# pt100.net
KiCad netlist of a schematic drawn in Altium Designer
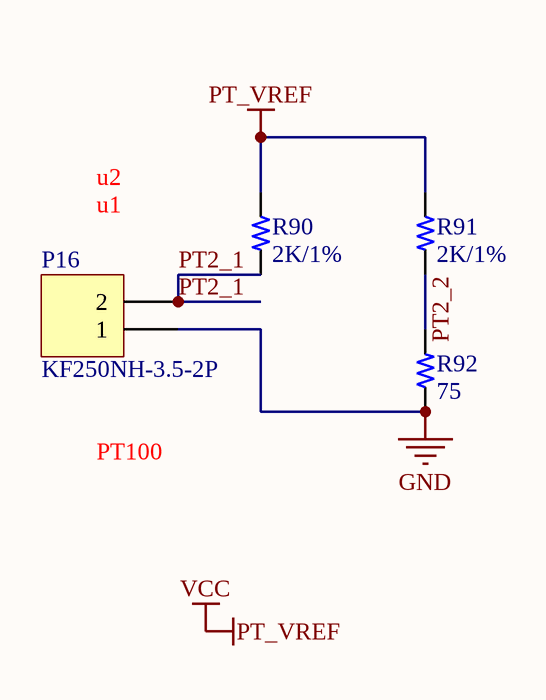
[diagram p0: pt100.SchDoc]

(export (version "E")
  (design (tool "Eeschema 10.0.6"))
  (components
    (comp (ref "P16")
      (value "KF250NH-3.5-2P")
      (footprint "KF250NH-3.5-2P")
      (fields (field (name "PUBLISHER") "Altium Limited"))
      (libsource (lib "Miscellaneous Connectors") (part "Header 2"))
    )
    (comp (ref "R90") (value "2K/1%") (footprint "0603R") (libsource (lib "JRJ_1") (part "R")))
    (comp (ref "R91") (value "2K/1%") (footprint "0603R") (libsource (lib "JRJ_1") (part "R")))
    (comp (ref "R92") (value "75") (footprint "0603R") (libsource (lib "JRJ_1") (part "R")))
  )
  (nets
    (net (code "1") (name "/PT2_1") (class "Default")
      (node (ref "P16") (pin "2") (pinfunction "2_2") (pintype "passive"))
      (node (ref "R90") (pin "1") (pintype "passive"))
    )
    (net (code "2") (name "/PT2_2") (class "Default")
      (node (ref "R91") (pin "1") (pintype "passive"))
      (node (ref "R92") (pin "2") (pintype "passive"))
    )
    (net (code "3") (name "GND") (class "Default")
      (node (ref "P16") (pin "1") (pinfunction "1_1") (pintype "passive"))
      (node (ref "R92") (pin "1") (pintype "passive"))
    )
    (net (code "4") (name "PT_VREF") (class "Default")
      (node (ref "R90") (pin "2") (pintype "passive"))
      (node (ref "R91") (pin "2") (pintype "passive"))
    )
  )
)
